# Prog_NRF52.net
KiCad netlist of a schematic drawn in EAGLE
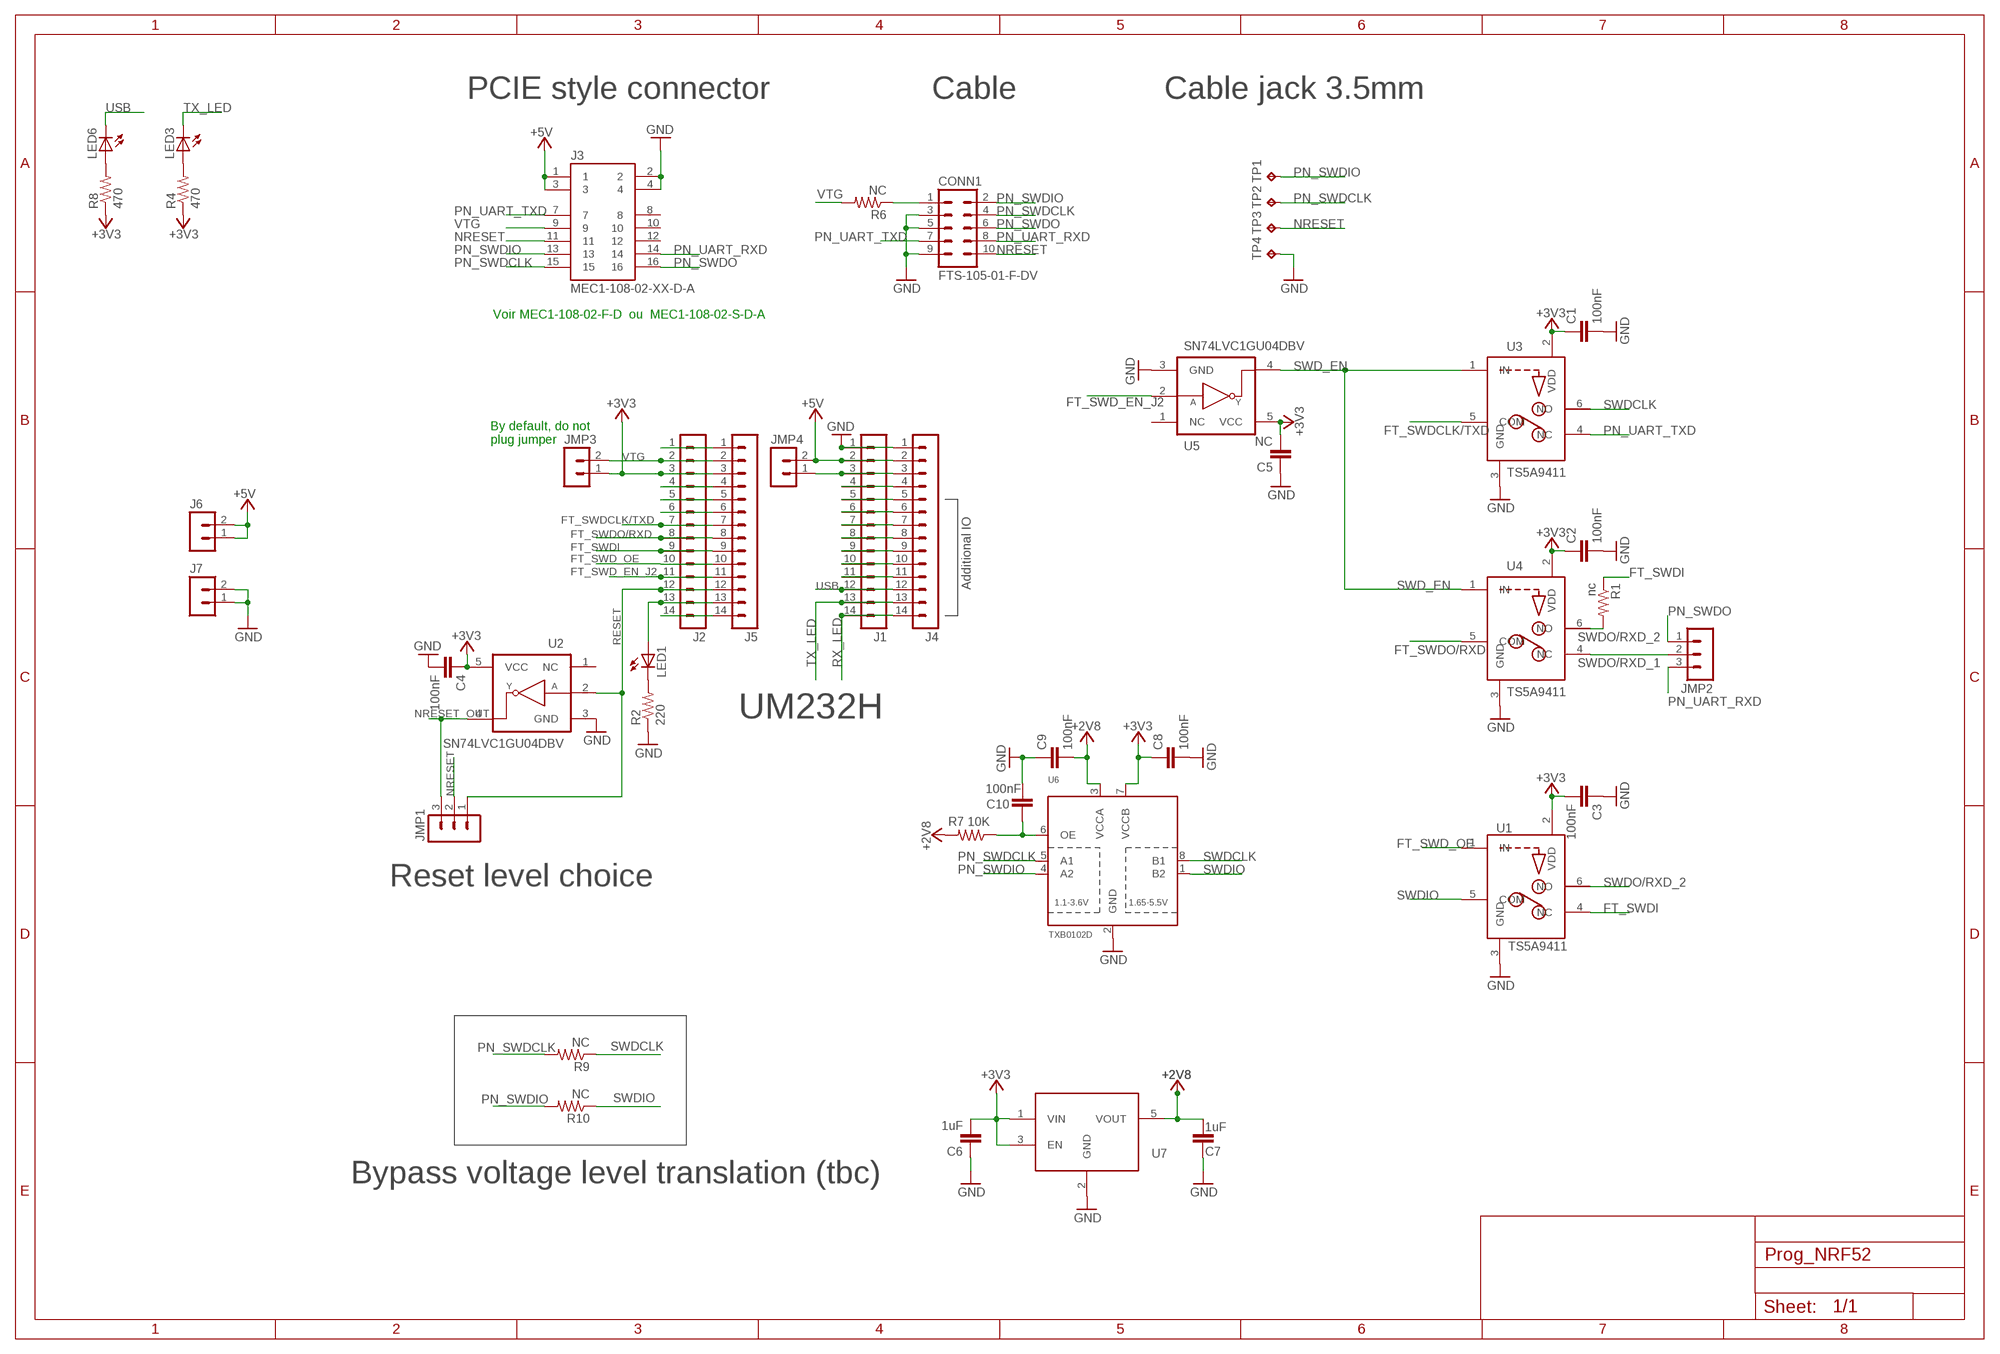
[diagram p0: schematic, sheet 1]

(export (version "E")
  (design (tool "Eeschema 10.0.6"))
  (components
    (comp (ref "C1")
      (value "100nF")
      (footprint "eagle-import:C0603K")
      (libsource (lib "eagle-import") (part "C-EUC0603K"))
    )
    (comp (ref "C2")
      (value "100nF")
      (footprint "eagle-import:C0603K")
      (libsource (lib "eagle-import") (part "C-EUC0603K"))
    )
    (comp (ref "C3")
      (value "100nF")
      (footprint "eagle-import:C0603K")
      (libsource (lib "eagle-import") (part "C-EUC0603K"))
    )
    (comp (ref "C4")
      (value "100nF")
      (footprint "eagle-import:C0603K")
      (libsource (lib "eagle-import") (part "C-EUC0603K"))
    )
    (comp (ref "C5")
      (value "NC")
      (footprint "eagle-import:C0603K")
      (libsource (lib "eagle-import") (part "C-EUC0603K"))
    )
    (comp (ref "C6")
      (value "1uF")
      (footprint "eagle-import:C0603K")
      (libsource (lib "eagle-import") (part "C-EUC0603K"))
    )
    (comp (ref "C7")
      (value "1uF")
      (footprint "eagle-import:C0603K")
      (libsource (lib "eagle-import") (part "C-EUC0603K"))
    )
    (comp (ref "C8")
      (value "100nF")
      (footprint "eagle-import:C0603K")
      (libsource (lib "eagle-import") (part "C-EUC0603K"))
    )
    (comp (ref "C9")
      (value "100nF")
      (footprint "eagle-import:C0603K")
      (libsource (lib "eagle-import") (part "C-EUC0603K"))
    )
    (comp (ref "C10")
      (value "100nF")
      (footprint "eagle-import:C0603K")
      (libsource (lib "eagle-import") (part "C-EUC0603K"))
    )
    (comp (ref "CONN1")
      (value "FTS-105-01-F-DV")
      (footprint "eagle-import:FTS-105-01-F-DV")
      (libsource (lib "eagle-import") (part "FTS-105-01-F-DV"))
    )
    (comp (ref "J1")
      (value "MA14-1")
      (footprint "eagle-import:MA14-1")
      (libsource (lib "eagle-import") (part "MA14-1"))
    )
    (comp (ref "J2")
      (value "MA14-1")
      (footprint "eagle-import:MA14-1")
      (libsource (lib "eagle-import") (part "MA14-1"))
    )
    (comp (ref "J3")
      (value "MEC1-108-02-XX-D-A")
      (footprint "eagle-import:MEC1-108-02-XX-D-A")
      (libsource (lib "eagle-import") (part "MEC1-108-02-XX-D-A"))
    )
    (comp (ref "J4")
      (value "MA14-1")
      (footprint "eagle-import:MA14-1")
      (libsource (lib "eagle-import") (part "MA14-1"))
    )
    (comp (ref "J5")
      (value "MA14-1")
      (footprint "eagle-import:MA14-1")
      (libsource (lib "eagle-import") (part "MA14-1"))
    )
    (comp (ref "J6")
      (value "MA02-1")
      (footprint "eagle-import:MA02-1")
      (libsource (lib "eagle-import") (part "MA02-1"))
    )
    (comp (ref "J7")
      (value "MA02-1")
      (footprint "eagle-import:MA02-1")
      (libsource (lib "eagle-import") (part "MA02-1"))
    )
    (comp (ref "JMP1")
      (value "MA03-1")
      (footprint "eagle-import:MA03-1")
      (libsource (lib "eagle-import") (part "MA03-1"))
    )
    (comp (ref "JMP2")
      (value "MA03-1")
      (footprint "eagle-import:MA03-1")
      (libsource (lib "eagle-import") (part "MA03-1"))
    )
    (comp (ref "JMP3")
      (value "MA02-1")
      (footprint "eagle-import:MA02-1")
      (libsource (lib "eagle-import") (part "MA02-1"))
    )
    (comp (ref "JMP4")
      (value "MA02-1")
      (footprint "eagle-import:MA02-1")
      (libsource (lib "eagle-import") (part "MA02-1"))
    )
    (comp (ref "LED1")
      (value "LEDCHIP-LED0603")
      (footprint "eagle-import:CHIP-LED0603")
      (libsource (lib "eagle-import") (part "LEDCHIP-LED0603"))
    )
    (comp (ref "LED3")
      (value "LEDCHIP-LED0603")
      (footprint "eagle-import:CHIP-LED0603")
      (libsource (lib "eagle-import") (part "LEDCHIP-LED0603"))
    )
    (comp (ref "LED6")
      (value "LEDCHIP-LED0603")
      (footprint "eagle-import:CHIP-LED0603")
      (libsource (lib "eagle-import") (part "LEDCHIP-LED0603"))
    )
    (comp (ref "R1")
      (value "nc")
      (footprint "eagle-import:R0603")
      (libsource (lib "eagle-import") (part "R-US_R0603"))
    )
    (comp (ref "R2")
      (value "220")
      (footprint "eagle-import:R0603")
      (libsource (lib "eagle-import") (part "R-US_R0603"))
    )
    (comp (ref "R4")
      (value "470")
      (footprint "eagle-import:R0603")
      (libsource (lib "eagle-import") (part "R-US_R0603"))
    )
    (comp (ref "R6")
      (value "NC")
      (footprint "eagle-import:R0603")
      (libsource (lib "eagle-import") (part "R-US_R0603"))
    )
    (comp (ref "R7")
      (value "10K")
      (footprint "eagle-import:R0603")
      (libsource (lib "eagle-import") (part "R-US_R0603"))
    )
    (comp (ref "R8")
      (value "470")
      (footprint "eagle-import:R0603")
      (libsource (lib "eagle-import") (part "R-US_R0603"))
    )
    (comp (ref "R9")
      (value "NC")
      (footprint "eagle-import:R0603")
      (libsource (lib "eagle-import") (part "R-US_R0603"))
    )
    (comp (ref "R10")
      (value "NC")
      (footprint "eagle-import:R0603")
      (libsource (lib "eagle-import") (part "R-US_R0603"))
    )
    (comp (ref "TP1")
      (value "TPPAD1-13")
      (footprint "eagle-import:P1-13")
      (libsource (lib "eagle-import") (part "TPPAD1-13"))
    )
    (comp (ref "TP2")
      (value "TPPAD1-13")
      (footprint "eagle-import:P1-13")
      (libsource (lib "eagle-import") (part "TPPAD1-13"))
    )
    (comp (ref "TP3")
      (value "TPPAD1-13")
      (footprint "eagle-import:P1-13")
      (libsource (lib "eagle-import") (part "TPPAD1-13"))
    )
    (comp (ref "TP4")
      (value "TPPAD1-13")
      (footprint "eagle-import:P1-13")
      (libsource (lib "eagle-import") (part "TPPAD1-13"))
    )
    (comp (ref "U1")
      (value "TS5A9411")
      (footprint "eagle-import:SC70-6")
      (libsource (lib "eagle-import") (part "TS5A9411"))
    )
    (comp (ref "U2")
      (value "SN74LVC1GU04DBV")
      (footprint "eagle-import:SOT23-5")
      (libsource (lib "eagle-import") (part "SN74LVC1GU04DBV"))
    )
    (comp (ref "U3")
      (value "TS5A9411")
      (footprint "eagle-import:SC70-6")
      (libsource (lib "eagle-import") (part "TS5A9411"))
    )
    (comp (ref "U4")
      (value "TS5A9411")
      (footprint "eagle-import:SC70-6")
      (libsource (lib "eagle-import") (part "TS5A9411"))
    )
    (comp (ref "U5")
      (value "SN74LVC1GU04DBV")
      (footprint "eagle-import:SOT23-5")
      (libsource (lib "eagle-import") (part "SN74LVC1GU04DBV"))
    )
    (comp (ref "U6")
      (value "TXB0102D")
      (footprint "eagle-import:VSSOP8")
      (libsource (lib "eagle-import") (part "TXB0102D"))
    )
    (comp (ref "U7")
      (value "NCP114ASN280T1G")
      (footprint "eagle-import:SOT23-5")
      (libsource (lib "eagle-import") (part "NCP114ASN280T1G"))
    )
  )
  (nets
    (net (code "1") (name "+2V8") (class "Default")
      (node (ref "C7") (pin "2") (pinfunction "2_2") (pintype "passive"))
      (node (ref "C9") (pin "2") (pinfunction "2_2") (pintype "passive"))
      (node (ref "R7") (pin "2") (pinfunction "2_2") (pintype "passive"))
      (node (ref "U6") (pin "3") (pinfunction "VCCA_3") (pintype "bidirectional"))
      (node (ref "U7") (pin "5") (pinfunction "VOUT_5") (pintype "output"))
    )
    (net (code "2") (name "+3V3") (class "Default")
      (node (ref "C1") (pin "1") (pinfunction "1_1") (pintype "passive"))
      (node (ref "C2") (pin "1") (pinfunction "1_1") (pintype "passive"))
      (node (ref "C3") (pin "2") (pinfunction "2_2") (pintype "passive"))
      (node (ref "C4") (pin "1") (pinfunction "1_1") (pintype "passive"))
      (node (ref "C5") (pin "2") (pinfunction "2_2") (pintype "passive"))
      (node (ref "C6") (pin "2") (pinfunction "2_2") (pintype "passive"))
      (node (ref "C8") (pin "1") (pinfunction "1_1") (pintype "passive"))
      (node (ref "J2") (pin "3") (pinfunction "3_3") (pintype "passive"))
      (node (ref "J5") (pin "3") (pinfunction "3_3") (pintype "passive"))
      (node (ref "JMP3") (pin "1") (pinfunction "1_1") (pintype "passive"))
      (node (ref "R4") (pin "1") (pinfunction "1_1") (pintype "passive"))
      (node (ref "R8") (pin "1") (pinfunction "1_1") (pintype "passive"))
      (node (ref "U1") (pin "2") (pinfunction "VDD_2") (pintype "power_in"))
      (node (ref "U2") (pin "5") (pinfunction "VCC_5") (pintype "power_in"))
      (node (ref "U3") (pin "2") (pinfunction "VDD_2") (pintype "power_in"))
      (node (ref "U4") (pin "2") (pinfunction "VDD_2") (pintype "power_in"))
      (node (ref "U5") (pin "5") (pinfunction "VCC_5") (pintype "power_in"))
      (node (ref "U6") (pin "7") (pinfunction "VCCB_7") (pintype "bidirectional"))
      (node (ref "U7") (pin "1") (pinfunction "VIN_1") (pintype "input"))
      (node (ref "U7") (pin "3") (pinfunction "EN_3") (pintype "input"))
    )
    (net (code "3") (name "+5V") (class "Default")
      (node (ref "J1") (pin "2") (pinfunction "2_2") (pintype "passive"))
      (node (ref "J3") (pin "1") (pinfunction "1_1") (pintype "bidirectional"))
      (node (ref "J3") (pin "3") (pinfunction "3_3") (pintype "bidirectional"))
      (node (ref "J4") (pin "2") (pinfunction "2_2") (pintype "passive"))
      (node (ref "J6") (pin "1") (pinfunction "1_1") (pintype "passive"))
      (node (ref "J6") (pin "2") (pinfunction "2_2") (pintype "passive"))
      (node (ref "JMP4") (pin "2") (pinfunction "2_2") (pintype "passive"))
    )
    (net (code "4") (name "/FT_SWDCLK{slash}TXD") (class "Default")
      (node (ref "J2") (pin "7") (pinfunction "7_7") (pintype "passive"))
      (node (ref "J5") (pin "7") (pinfunction "7_7") (pintype "passive"))
      (node (ref "U3") (pin "5") (pinfunction "COM_5") (pintype "bidirectional"))
    )
    (net (code "5") (name "/FT_SWDI") (class "Default")
      (node (ref "J2") (pin "9") (pinfunction "9_9") (pintype "passive"))
      (node (ref "J5") (pin "9") (pinfunction "9_9") (pintype "passive"))
      (node (ref "R1") (pin "1") (pinfunction "1_1") (pintype "passive"))
      (node (ref "U1") (pin "4") (pinfunction "NC_4") (pintype "bidirectional"))
    )
    (net (code "6") (name "/FT_SWDO{slash}RXD") (class "Default")
      (node (ref "J2") (pin "8") (pinfunction "8_8") (pintype "passive"))
      (node (ref "J5") (pin "8") (pinfunction "8_8") (pintype "passive"))
      (node (ref "U4") (pin "5") (pinfunction "COM_5") (pintype "bidirectional"))
    )
    (net (code "7") (name "/FT_SWD_EN_J2") (class "Default")
      (node (ref "J2") (pin "11") (pinfunction "11_11") (pintype "passive"))
      (node (ref "J5") (pin "11") (pinfunction "11_11") (pintype "passive"))
      (node (ref "U5") (pin "2") (pinfunction "A_2") (pintype "input"))
    )
    (net (code "8") (name "/FT_SWD_OE") (class "Default")
      (node (ref "J2") (pin "10") (pinfunction "10_10") (pintype "passive"))
      (node (ref "J5") (pin "10") (pinfunction "10_10") (pintype "passive"))
      (node (ref "U1") (pin "1") (pinfunction "IN_1") (pintype "input"))
    )
    (net (code "9") (name "/NRESET") (class "Default")
      (node (ref "CONN1") (pin "10") (pinfunction "10_10") (pintype "passive"))
      (node (ref "J3") (pin "11") (pinfunction "11_11") (pintype "bidirectional"))
      (node (ref "JMP1") (pin "2") (pinfunction "2_2") (pintype "passive"))
      (node (ref "TP3") (pin "TP") (pinfunction "TP_TP") (pintype "input"))
    )
    (net (code "10") (name "/NRESET_OUT") (class "Default")
      (node (ref "JMP1") (pin "3") (pinfunction "3_3") (pintype "passive"))
      (node (ref "U2") (pin "4") (pinfunction "Y_4") (pintype "output"))
    )
    (net (code "11") (name "/PN_SWDCLK") (class "Default")
      (node (ref "CONN1") (pin "4") (pinfunction "4_4") (pintype "passive"))
      (node (ref "J3") (pin "15") (pinfunction "15_15") (pintype "bidirectional"))
      (node (ref "R9") (pin "2") (pinfunction "2_2") (pintype "passive"))
      (node (ref "TP2") (pin "TP") (pinfunction "TP_TP") (pintype "input"))
      (node (ref "U6") (pin "5") (pinfunction "A1_5") (pintype "bidirectional"))
    )
    (net (code "12") (name "/PN_SWDIO") (class "Default")
      (node (ref "CONN1") (pin "2") (pinfunction "2_2") (pintype "passive"))
      (node (ref "J3") (pin "13") (pinfunction "13_13") (pintype "bidirectional"))
      (node (ref "R10") (pin "2") (pinfunction "2_2") (pintype "passive"))
      (node (ref "TP1") (pin "TP") (pinfunction "TP_TP") (pintype "input"))
      (node (ref "U6") (pin "4") (pinfunction "A2_4") (pintype "bidirectional"))
    )
    (net (code "13") (name "/PN_SWDO") (class "Default")
      (node (ref "CONN1") (pin "6") (pinfunction "6_6") (pintype "passive"))
      (node (ref "J3") (pin "16") (pinfunction "16_16") (pintype "bidirectional"))
      (node (ref "JMP2") (pin "1") (pinfunction "1_1") (pintype "passive"))
    )
    (net (code "14") (name "/PN_UART_RXD") (class "Default")
      (node (ref "CONN1") (pin "8") (pinfunction "8_8") (pintype "passive"))
      (node (ref "J3") (pin "14") (pinfunction "14_14") (pintype "bidirectional"))
      (node (ref "JMP2") (pin "3") (pinfunction "3_3") (pintype "passive"))
    )
    (net (code "15") (name "/PN_UART_TXD") (class "Default")
      (node (ref "CONN1") (pin "7") (pinfunction "7_7") (pintype "passive"))
      (node (ref "J3") (pin "7") (pinfunction "7_7") (pintype "bidirectional"))
      (node (ref "U3") (pin "4") (pinfunction "NC_4") (pintype "bidirectional"))
    )
    (net (code "16") (name "/RESET") (class "Default")
      (node (ref "J2") (pin "12") (pinfunction "12_12") (pintype "passive"))
      (node (ref "J5") (pin "12") (pinfunction "12_12") (pintype "passive"))
      (node (ref "JMP1") (pin "1") (pinfunction "1_1") (pintype "passive"))
      (node (ref "U2") (pin "2") (pinfunction "A_2") (pintype "input"))
    )
    (net (code "17") (name "/RX_LED") (class "Default")
      (node (ref "J1") (pin "14") (pinfunction "14_14") (pintype "passive"))
      (node (ref "J4") (pin "14") (pinfunction "14_14") (pintype "passive"))
    )
    (net (code "18") (name "/SWDCLK") (class "Default")
      (node (ref "R9") (pin "1") (pinfunction "1_1") (pintype "passive"))
      (node (ref "U3") (pin "6") (pinfunction "NO_6") (pintype "bidirectional"))
      (node (ref "U6") (pin "8") (pinfunction "B1_8") (pintype "bidirectional"))
    )
    (net (code "19") (name "/SWDIO") (class "Default")
      (node (ref "R10") (pin "1") (pinfunction "1_1") (pintype "passive"))
      (node (ref "U1") (pin "5") (pinfunction "COM_5") (pintype "bidirectional"))
      (node (ref "U6") (pin "1") (pinfunction "B2_1") (pintype "bidirectional"))
    )
    (net (code "20") (name "/SWDO{slash}RXD_1") (class "Default")
      (node (ref "JMP2") (pin "2") (pinfunction "2_2") (pintype "passive"))
      (node (ref "U4") (pin "4") (pinfunction "NC_4") (pintype "bidirectional"))
    )
    (net (code "21") (name "/SWDO{slash}RXD_2") (class "Default")
      (node (ref "R1") (pin "2") (pinfunction "2_2") (pintype "passive"))
      (node (ref "U1") (pin "6") (pinfunction "NO_6") (pintype "bidirectional"))
      (node (ref "U4") (pin "6") (pinfunction "NO_6") (pintype "bidirectional"))
    )
    (net (code "22") (name "/SWD_EN") (class "Default")
      (node (ref "U3") (pin "1") (pinfunction "IN_1") (pintype "input"))
      (node (ref "U4") (pin "1") (pinfunction "IN_1") (pintype "input"))
      (node (ref "U5") (pin "4") (pinfunction "Y_4") (pintype "output"))
    )
    (net (code "23") (name "/TX_LED") (class "Default")
      (node (ref "J1") (pin "13") (pinfunction "13_13") (pintype "passive"))
      (node (ref "J4") (pin "13") (pinfunction "13_13") (pintype "passive"))
      (node (ref "LED3") (pin "C") (pinfunction "C_C") (pintype "passive"))
    )
    (net (code "24") (name "/USB") (class "Default")
      (node (ref "J1") (pin "12") (pinfunction "12_12") (pintype "passive"))
      (node (ref "J4") (pin "12") (pinfunction "12_12") (pintype "passive"))
      (node (ref "LED6") (pin "C") (pinfunction "C_C") (pintype "passive"))
    )
    (net (code "25") (name "/VTG") (class "Default")
      (node (ref "J2") (pin "2") (pinfunction "2_2") (pintype "passive"))
      (node (ref "J3") (pin "9") (pinfunction "9_9") (pintype "bidirectional"))
      (node (ref "J5") (pin "2") (pinfunction "2_2") (pintype "passive"))
      (node (ref "JMP3") (pin "2") (pinfunction "2_2") (pintype "passive"))
      (node (ref "R6") (pin "2") (pinfunction "2_2") (pintype "passive"))
    )
    (net (code "26") (name "GND") (class "Default")
      (node (ref "C1") (pin "2") (pinfunction "2_2") (pintype "passive"))
      (node (ref "C10") (pin "2") (pinfunction "2_2") (pintype "passive"))
      (node (ref "C2") (pin "2") (pinfunction "2_2") (pintype "passive"))
      (node (ref "C3") (pin "1") (pinfunction "1_1") (pintype "passive"))
      (node (ref "C4") (pin "2") (pinfunction "2_2") (pintype "passive"))
      (node (ref "C5") (pin "1") (pinfunction "1_1") (pintype "passive"))
      (node (ref "C6") (pin "1") (pinfunction "1_1") (pintype "passive"))
      (node (ref "C7") (pin "1") (pinfunction "1_1") (pintype "passive"))
      (node (ref "C8") (pin "2") (pinfunction "2_2") (pintype "passive"))
      (node (ref "C9") (pin "1") (pinfunction "1_1") (pintype "passive"))
      (node (ref "CONN1") (pin "3") (pinfunction "3_3") (pintype "passive"))
      (node (ref "CONN1") (pin "5") (pinfunction "5_5") (pintype "passive"))
      (node (ref "CONN1") (pin "9") (pinfunction "9_9") (pintype "passive"))
      (node (ref "J1") (pin "1") (pinfunction "1_1") (pintype "passive"))
      (node (ref "J3") (pin "2") (pinfunction "2_2") (pintype "bidirectional"))
      (node (ref "J3") (pin "4") (pinfunction "4_4") (pintype "bidirectional"))
      (node (ref "J4") (pin "1") (pinfunction "1_1") (pintype "passive"))
      (node (ref "J7") (pin "1") (pinfunction "1_1") (pintype "passive"))
      (node (ref "J7") (pin "2") (pinfunction "2_2") (pintype "passive"))
      (node (ref "R2") (pin "1") (pinfunction "1_1") (pintype "passive"))
      (node (ref "TP4") (pin "TP") (pinfunction "TP_TP") (pintype "input"))
      (node (ref "U1") (pin "3") (pinfunction "GND_3") (pintype "power_in"))
      (node (ref "U2") (pin "3") (pinfunction "GND_3") (pintype "power_in"))
      (node (ref "U3") (pin "3") (pinfunction "GND_3") (pintype "power_in"))
      (node (ref "U4") (pin "3") (pinfunction "GND_3") (pintype "power_in"))
      (node (ref "U5") (pin "3") (pinfunction "GND_3") (pintype "power_in"))
      (node (ref "U6") (pin "2") (pinfunction "GND_2") (pintype "bidirectional"))
      (node (ref "U7") (pin "2") (pinfunction "GND_2") (pintype "power_in"))
    )
    (net (code "27") (name "Net-(CONN1-Pad1)") (class "Default")
      (node (ref "CONN1") (pin "1") (pinfunction "1_1") (pintype "passive"))
      (node (ref "R6") (pin "1") (pinfunction "1_1") (pintype "passive"))
    )
    (net (code "28") (name "Net-(J1-Pad3)") (class "Default")
      (node (ref "J1") (pin "3") (pinfunction "3_3") (pintype "passive"))
      (node (ref "J4") (pin "3") (pinfunction "3_3") (pintype "passive"))
      (node (ref "JMP4") (pin "1") (pinfunction "1_1") (pintype "passive"))
    )
    (net (code "29") (name "Net-(J1-Pad4)") (class "Default")
      (node (ref "J1") (pin "4") (pinfunction "4_4") (pintype "passive"))
      (node (ref "J4") (pin "4") (pinfunction "4_4") (pintype "passive"))
    )
    (net (code "30") (name "Net-(J1-Pad5)") (class "Default")
      (node (ref "J1") (pin "5") (pinfunction "5_5") (pintype "passive"))
      (node (ref "J4") (pin "5") (pinfunction "5_5") (pintype "passive"))
    )
    (net (code "31") (name "Net-(J1-Pad6)") (class "Default")
      (node (ref "J1") (pin "6") (pinfunction "6_6") (pintype "passive"))
      (node (ref "J4") (pin "6") (pinfunction "6_6") (pintype "passive"))
    )
    (net (code "32") (name "Net-(J1-Pad7)") (class "Default")
      (node (ref "J1") (pin "7") (pinfunction "7_7") (pintype "passive"))
      (node (ref "J4") (pin "7") (pinfunction "7_7") (pintype "passive"))
    )
    (net (code "33") (name "Net-(J1-Pad8)") (class "Default")
      (node (ref "J1") (pin "8") (pinfunction "8_8") (pintype "passive"))
      (node (ref "J4") (pin "8") (pinfunction "8_8") (pintype "passive"))
    )
    (net (code "34") (name "Net-(J1-Pad9)") (class "Default")
      (node (ref "J1") (pin "9") (pinfunction "9_9") (pintype "passive"))
      (node (ref "J4") (pin "9") (pinfunction "9_9") (pintype "passive"))
    )
    (net (code "35") (name "Net-(J1-Pad10)") (class "Default")
      (node (ref "J1") (pin "10") (pinfunction "10_10") (pintype "passive"))
      (node (ref "J4") (pin "10") (pinfunction "10_10") (pintype "passive"))
    )
    (net (code "36") (name "Net-(J1-Pad11)") (class "Default")
      (node (ref "J1") (pin "11") (pinfunction "11_11") (pintype "passive"))
      (node (ref "J4") (pin "11") (pinfunction "11_11") (pintype "passive"))
    )
    (net (code "37") (name "Net-(J2-Pad1)") (class "Default")
      (node (ref "J2") (pin "1") (pinfunction "1_1") (pintype "passive"))
      (node (ref "J5") (pin "1") (pinfunction "1_1") (pintype "passive"))
    )
    (net (code "38") (name "Net-(J2-Pad4)") (class "Default")
      (node (ref "J2") (pin "4") (pinfunction "4_4") (pintype "passive"))
      (node (ref "J5") (pin "4") (pinfunction "4_4") (pintype "passive"))
    )
    (net (code "39") (name "Net-(J2-Pad5)") (class "Default")
      (node (ref "J2") (pin "5") (pinfunction "5_5") (pintype "passive"))
      (node (ref "J5") (pin "5") (pinfunction "5_5") (pintype "passive"))
    )
    (net (code "40") (name "Net-(J2-Pad6)") (class "Default")
      (node (ref "J2") (pin "6") (pinfunction "6_6") (pintype "passive"))
      (node (ref "J5") (pin "6") (pinfunction "6_6") (pintype "passive"))
    )
    (net (code "41") (name "Net-(J2-Pad13)") (class "Default")
      (node (ref "J2") (pin "13") (pinfunction "13_13") (pintype "passive"))
      (node (ref "J5") (pin "13") (pinfunction "13_13") (pintype "passive"))
      (node (ref "LED1") (pin "A") (pinfunction "A_A") (pintype "passive"))
    )
    (net (code "42") (name "Net-(J2-Pad14)") (class "Default")
      (node (ref "J2") (pin "14") (pinfunction "14_14") (pintype "passive"))
      (node (ref "J5") (pin "14") (pinfunction "14_14") (pintype "passive"))
    )
    (net (code "43") (name "Net-(LED1-PadC)") (class "Default")
      (node (ref "LED1") (pin "C") (pinfunction "C_C") (pintype "passive"))
      (node (ref "R2") (pin "2") (pinfunction "2_2") (pintype "passive"))
    )
    (net (code "44") (name "Net-(LED3-PadA)") (class "Default")
      (node (ref "LED3") (pin "A") (pinfunction "A_A") (pintype "passive"))
      (node (ref "R4") (pin "2") (pinfunction "2_2") (pintype "passive"))
    )
    (net (code "45") (name "Net-(LED6-PadA)") (class "Default")
      (node (ref "LED6") (pin "A") (pinfunction "A_A") (pintype "passive"))
      (node (ref "R8") (pin "2") (pinfunction "2_2") (pintype "passive"))
    )
    (net (code "46") (name "Net-(U6-OE)") (class "Default")
      (node (ref "C10") (pin "1") (pinfunction "1_1") (pintype "passive"))
      (node (ref "R7") (pin "1") (pinfunction "1_1") (pintype "passive"))
      (node (ref "U6") (pin "6") (pinfunction "OE_6") (pintype "bidirectional"))
    )
    (net (code "47") (name "unconnected-(J3-Pad8)") (class "Default")
      (node (ref "J3") (pin "8") (pinfunction "8_8") (pintype "bidirectional"))
    )
    (net (code "48") (name "unconnected-(J3-Pad10)") (class "Default")
      (node (ref "J3") (pin "10") (pinfunction "10_10") (pintype "bidirectional"))
    )
    (net (code "49") (name "unconnected-(J3-Pad12)") (class "Default")
      (node (ref "J3") (pin "12") (pinfunction "12_12") (pintype "bidirectional"))
    )
    (net (code "50") (name "unconnected-(U2-NC-Pad1)") (class "Default")
      (node (ref "U2") (pin "1") (pinfunction "NC_1") (pintype "no_connect"))
    )
    (net (code "51") (name "unconnected-(U5-NC-Pad1)") (class "Default")
      (node (ref "U5") (pin "1") (pinfunction "NC_1") (pintype "no_connect"))
    )
  )
)
